# DOORLOCK_v3.net
KiCad netlist of a schematic drawn in EAGLE
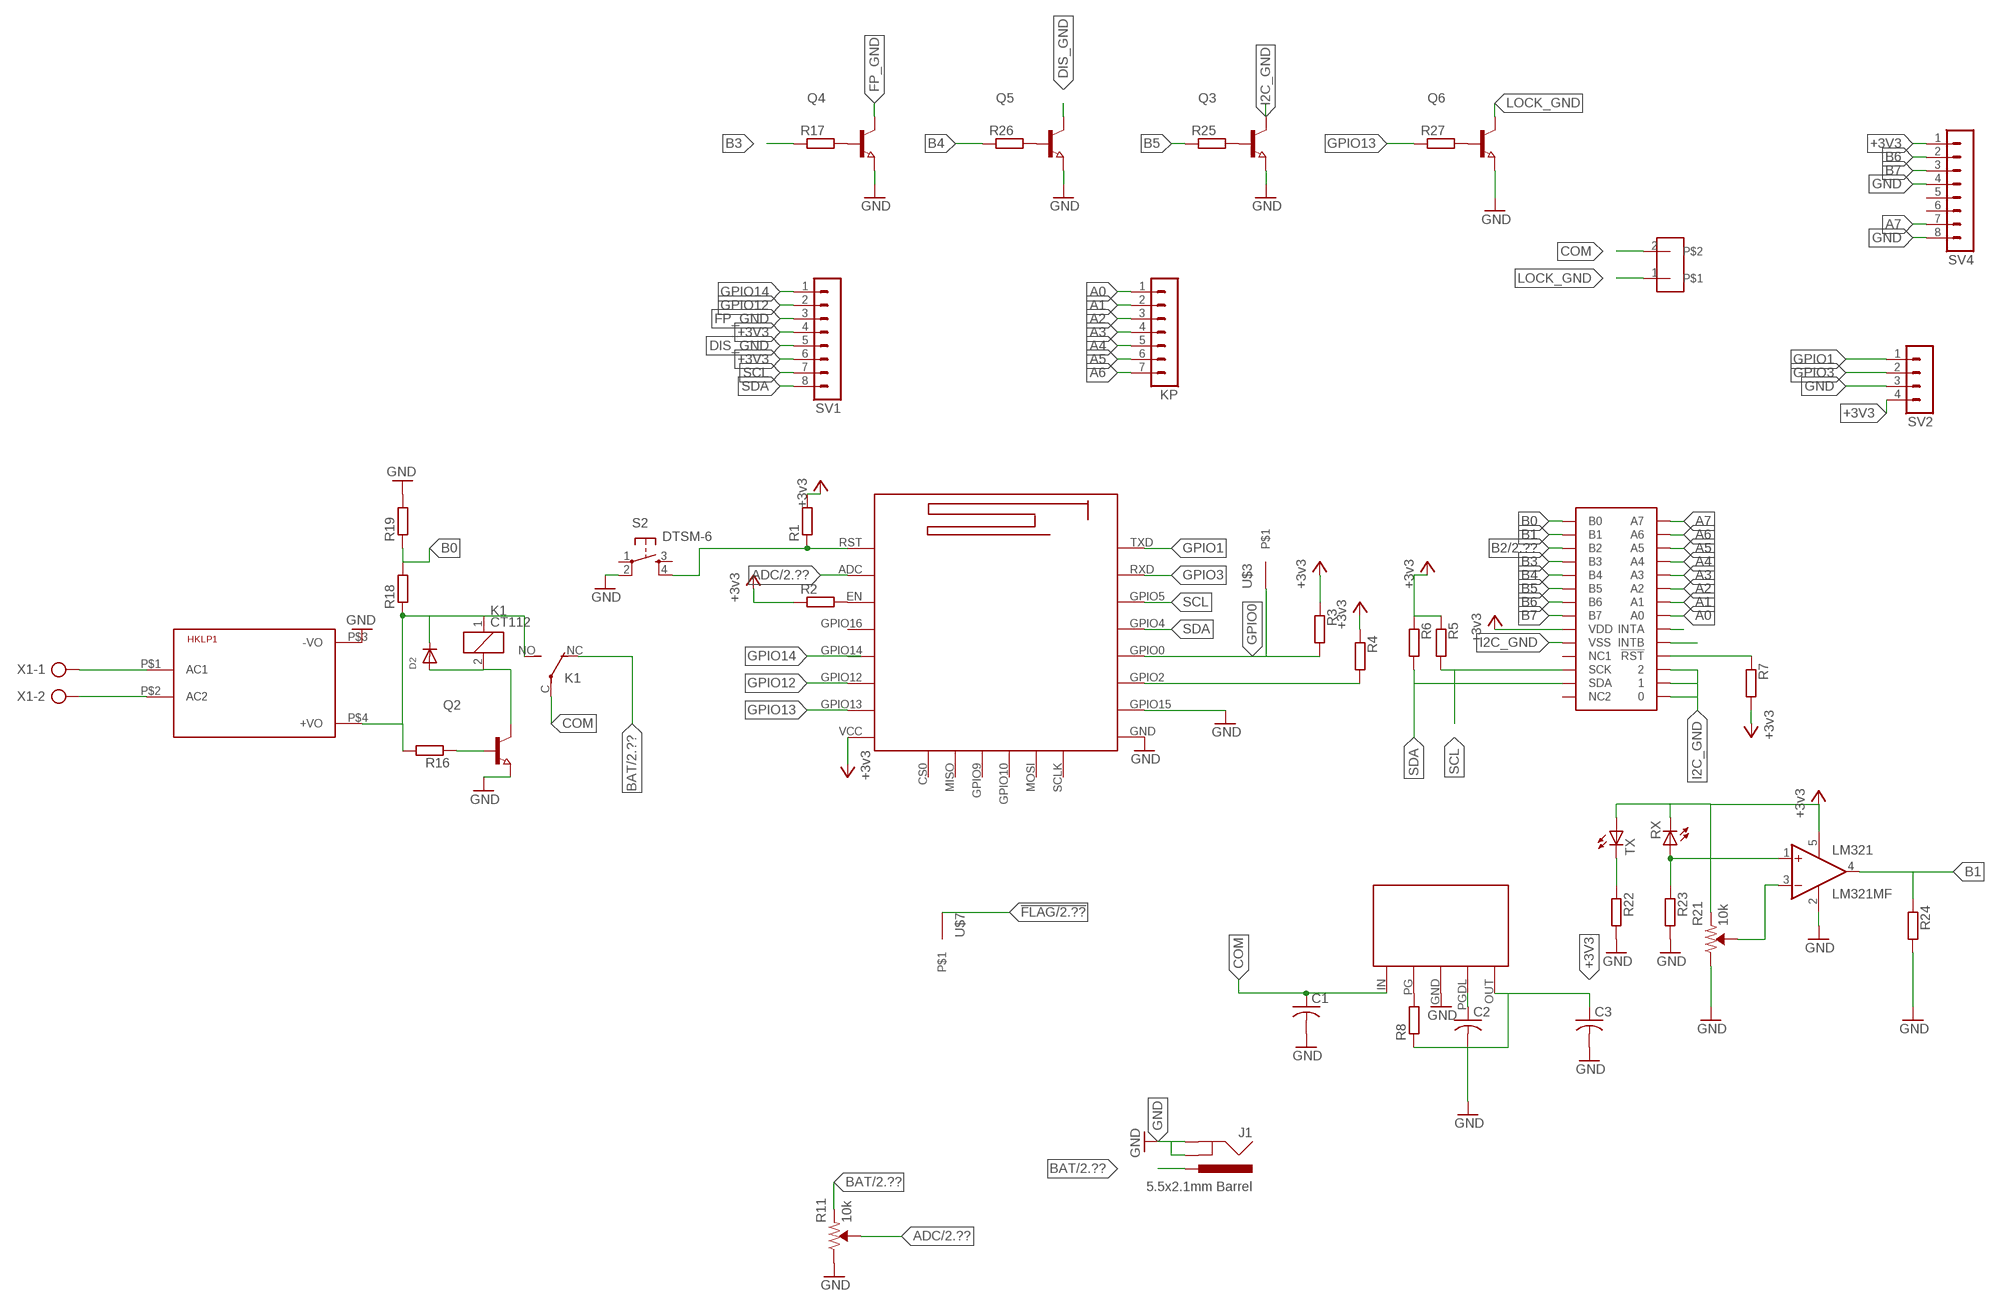
[diagram p0: schematic, sheet 1]
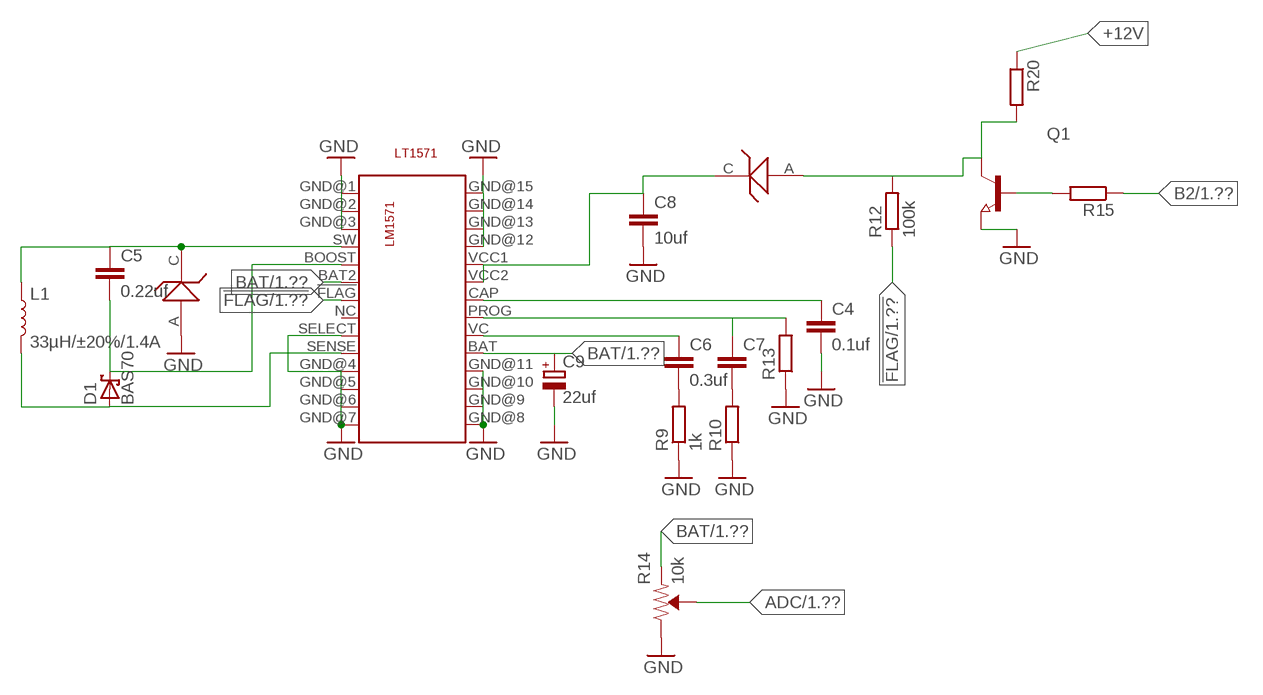
[diagram p1: schematic, sheet 2]

(export (version "E")
  (design (tool "Eeschema 10.0.6"))
  (components
    (comp (ref "C4")
      (value "0.1uf")
      (footprint "eagle-import:C0805")
      (libsource (lib "eagle-import") (part "C-EUC0805"))
    )
    (comp (ref "C5")
      (value "0.22uf")
      (footprint "eagle-import:C0805")
      (libsource (lib "eagle-import") (part "C-EUC0805"))
    )
    (comp (ref "C6")
      (value "0.3uf")
      (footprint "eagle-import:C0805")
      (libsource (lib "eagle-import") (part "C-EUC0805"))
    )
    (comp (ref "C7")
      (value "C-EUC0805")
      (footprint "eagle-import:C0805")
      (libsource (lib "eagle-import") (part "C-EUC0805"))
    )
    (comp (ref "C8")
      (value "10uf")
      (footprint "eagle-import:C0805")
      (libsource (lib "eagle-import") (part "C-EUC0805"))
    )
    (comp (ref "C9")
      (value "22uf")
      (footprint "eagle-import:CT3216")
      (libsource (lib "eagle-import") (part "CPOL-EUCT3216"))
    )
    (comp (ref "D1")
      (value "BAS70")
      (footprint "eagle-import:SOT23")
      (libsource (lib "eagle-import") (part "BAS70"))
    )
    (comp (ref "D3")
      (value "MBRM120T3")
      (footprint "eagle-import:MBRM120T3")
      (libsource (lib "eagle-import") (part "MBRM120T3"))
    )
    (comp (ref "L1")
      (value "33µH/±20%/1.4A")
      (footprint "eagle-import:SRN6045")
      (libsource (lib "eagle-import") (part "INDUCTOR-SRN6045-33UH"))
    )
    (comp (ref "LT1571")
      (value "LM1571")
      (footprint "eagle-import:LT1571")
      (libsource (lib "eagle-import") (part "LM1571"))
    )
    (comp (ref "Q1")
      (value "NPN-TRANSISTOR_SOT89")
      (footprint "eagle-import:SOT89")
      (libsource (lib "eagle-import") (part "NPN-TRANSISTOR_SOT89"))
    )
    (comp (ref "R9")
      (value "1k")
      (footprint "eagle-import:0204V")
      (libsource (lib "eagle-import") (part "R-EU_0204/2V"))
    )
    (comp (ref "R10")
      (value "R-EU_0204/2V")
      (footprint "eagle-import:0204V")
      (libsource (lib "eagle-import") (part "R-EU_0204/2V"))
    )
    (comp (ref "R12")
      (value "100k")
      (footprint "eagle-import:0204V")
      (libsource (lib "eagle-import") (part "R-EU_0204/2V"))
    )
    (comp (ref "R13")
      (value "R-EU_0204/2V")
      (footprint "eagle-import:0204V")
      (libsource (lib "eagle-import") (part "R-EU_0204/2V"))
    )
    (comp (ref "R14")
      (value "10k")
      (footprint "eagle-import:TRIMPOT-SMD-TC33X")
      (libsource (lib "eagle-import") (part "TRIMPOT-SMD-3MM-OPEN-1/10W-25%"))
    )
    (comp (ref "R15")
      (value "R-EU_0204/2V")
      (footprint "eagle-import:0204V")
      (libsource (lib "eagle-import") (part "R-EU_0204/2V"))
    )
    (comp (ref "R20")
      (value "R-EU_0204/2V")
      (footprint "eagle-import:0204V")
      (libsource (lib "eagle-import") (part "R-EU_0204/2V"))
    )
    (comp (ref "U$6")
      (value "MBRM120T3")
      (footprint "eagle-import:MBRM120T3")
      (libsource (lib "eagle-import") (part "MBRM120T3"))
    )
    (comp (ref "C1")
      (value "C-USC1206")
      (footprint "eagle-import:C1206")
      (libsource (lib "eagle-import") (part "C-USC1206"))
    )
    (comp (ref "C2")
      (value "C-USC1206")
      (footprint "eagle-import:C1206")
      (libsource (lib "eagle-import") (part "C-USC1206"))
    )
    (comp (ref "C3")
      (value "C-USC1206")
      (footprint "eagle-import:C1206")
      (libsource (lib "eagle-import") (part "C-USC1206"))
    )
    (comp (ref "D2")
      (value "DIODESOD-123")
      (footprint "eagle-import:SOD-123")
      (libsource (lib "eagle-import") (part "DIODESOD-123"))
    )
    (comp (ref "HKLP1")
      (value "HKLPM01")
      (footprint "eagle-import:HKLPM01")
      (libsource (lib "eagle-import") (part "HKLPM01"))
    )
    (comp (ref "J1")
      (value "5.5x2.1mm Barrel")
      (footprint "eagle-import:POWER_JACK_SMD")
      (libsource (lib "eagle-import") (part "POWER_JACKSMD"))
    )
    (comp (ref "K1")
      (value "CT112")
      (footprint "eagle-import:CT-SLIM")
      (libsource (lib "eagle-import") (part "CT112"))
    )
    (comp (ref "KP")
      (value "MA07-1")
      (footprint "eagle-import:MA07-1")
      (libsource (lib "eagle-import") (part "MA07-1"))
    )
    (comp (ref "LM321")
      (value "LM321MF")
      (footprint "eagle-import:SOT23-5")
      (libsource (lib "eagle-import") (part "LM321?MF"))
    )
    (comp (ref "MCP23017")
      (value "MCF23017")
      (footprint "eagle-import:MAX23017")
      (libsource (lib "eagle-import") (part "MCF23017"))
    )
    (comp (ref "MP2014")
      (value "MP2014")
      (footprint "eagle-import:MP2014")
      (libsource (lib "eagle-import") (part "MP2014"))
    )
    (comp (ref "Q2")
      (value "NPN-TRANSISTOR_SOT89")
      (footprint "eagle-import:SOT89")
      (libsource (lib "eagle-import") (part "NPN-TRANSISTOR_SOT89"))
    )
    (comp (ref "Q3")
      (value "NPN-TRANSISTOR_SOT89")
      (footprint "eagle-import:SOT89")
      (libsource (lib "eagle-import") (part "NPN-TRANSISTOR_SOT89"))
    )
    (comp (ref "Q4")
      (value "NPN-TRANSISTOR_SOT89")
      (footprint "eagle-import:SOT89")
      (libsource (lib "eagle-import") (part "NPN-TRANSISTOR_SOT89"))
    )
    (comp (ref "Q5")
      (value "NPN-TRANSISTOR_SOT89")
      (footprint "eagle-import:SOT89")
      (libsource (lib "eagle-import") (part "NPN-TRANSISTOR_SOT89"))
    )
    (comp (ref "Q6")
      (value "NPN-TRANSISTOR_SOT89")
      (footprint "eagle-import:SOT89")
      (libsource (lib "eagle-import") (part "NPN-TRANSISTOR_SOT89"))
    )
    (comp (ref "R1")
      (value "R-EU_0204/2V")
      (footprint "eagle-import:0204V")
      (libsource (lib "eagle-import") (part "resistor_R-EU_0204/2V"))
    )
    (comp (ref "R2")
      (value "R-EU_0204/2V")
      (footprint "eagle-import:0204V")
      (libsource (lib "eagle-import") (part "resistor_R-EU_0204/2V"))
    )
    (comp (ref "R3")
      (value "R-EU_0204/2V")
      (footprint "eagle-import:0204V")
      (libsource (lib "eagle-import") (part "resistor_R-EU_0204/2V"))
    )
    (comp (ref "R4")
      (value "R-EU_0204/2V")
      (footprint "eagle-import:0204V")
      (libsource (lib "eagle-import") (part "resistor_R-EU_0204/2V"))
    )
    (comp (ref "R5")
      (value "R-EU_0204/2V")
      (footprint "eagle-import:0204V")
      (libsource (lib "eagle-import") (part "resistor_R-EU_0204/2V"))
    )
    (comp (ref "R6")
      (value "R-EU_0204/2V")
      (footprint "eagle-import:0204V")
      (libsource (lib "eagle-import") (part "resistor_R-EU_0204/2V"))
    )
    (comp (ref "R7")
      (value "R-EU_0204/2V")
      (footprint "eagle-import:0204V")
      (libsource (lib "eagle-import") (part "resistor_R-EU_0204/2V"))
    )
    (comp (ref "R8")
      (value "R-EU_0204/2V")
      (footprint "eagle-import:0204V")
      (libsource (lib "eagle-import") (part "resistor_R-EU_0204/2V"))
    )
    (comp (ref "R11")
      (value "10k")
      (footprint "eagle-import:TRIMPOT-SMD-TC33X")
      (libsource (lib "eagle-import") (part "TRIMPOT-SMD-3MM-OPEN-1/10W-25%"))
    )
    (comp (ref "R16")
      (value "R-EU_0204/2V")
      (footprint "eagle-import:0204V")
      (libsource (lib "eagle-import") (part "resistor_R-EU_0204/2V"))
    )
    (comp (ref "R17")
      (value "R-EU_0204/2V")
      (footprint "eagle-import:0204V")
      (libsource (lib "eagle-import") (part "resistor_R-EU_0204/2V"))
    )
    (comp (ref "R18")
      (value "R-EU_0204/2V")
      (footprint "eagle-import:0204V")
      (libsource (lib "eagle-import") (part "resistor_R-EU_0204/2V"))
    )
    (comp (ref "R19")
      (value "R-EU_0204/2V")
      (footprint "eagle-import:0204V")
      (libsource (lib "eagle-import") (part "resistor_R-EU_0204/2V"))
    )
    (comp (ref "R21")
      (value "10k")
      (footprint "eagle-import:TRIMPOT-SMD-TC33X")
      (libsource (lib "eagle-import") (part "TRIMPOT-SMD-3MM-OPEN-1/10W-25%"))
    )
    (comp (ref "R22")
      (value "R-EU_0204/2V")
      (footprint "eagle-import:0204V")
      (libsource (lib "eagle-import") (part "resistor_R-EU_0204/2V"))
    )
    (comp (ref "R23")
      (value "R-EU_0204/2V")
      (footprint "eagle-import:0204V")
      (libsource (lib "eagle-import") (part "resistor_R-EU_0204/2V"))
    )
    (comp (ref "R24")
      (value "R-EU_0204/2V")
      (footprint "eagle-import:0204V")
      (libsource (lib "eagle-import") (part "resistor_R-EU_0204/2V"))
    )
    (comp (ref "R25")
      (value "R-EU_0204/2V")
      (footprint "eagle-import:0204V")
      (libsource (lib "eagle-import") (part "resistor_R-EU_0204/2V"))
    )
    (comp (ref "R26")
      (value "R-EU_0204/2V")
      (footprint "eagle-import:0204V")
      (libsource (lib "eagle-import") (part "resistor_R-EU_0204/2V"))
    )
    (comp (ref "R27")
      (value "R-EU_0204/2V")
      (footprint "eagle-import:0204V")
      (libsource (lib "eagle-import") (part "resistor_R-EU_0204/2V"))
    )
    (comp (ref "RX")
      (value "LED5MM")
      (footprint "eagle-import:LED5MM")
      (libsource (lib "eagle-import") (part "LED5MM"))
    )
    (comp (ref "S2")
      (value "DTSM-6")
      (footprint "eagle-import:DTSM-6")
      (libsource (lib "eagle-import") (part "DTSM-6"))
    )
    (comp (ref "SV1")
      (value "MA08-1")
      (footprint "eagle-import:MA08-1")
      (libsource (lib "eagle-import") (part "MA08-1"))
    )
    (comp (ref "SV2")
      (value "MA04-1")
      (footprint "eagle-import:MA04-1")
      (libsource (lib "eagle-import") (part "MA04-1"))
    )
    (comp (ref "SV4")
      (value "MA08-1")
      (footprint "eagle-import:MA08-1")
      (libsource (lib "eagle-import") (part "MA08-1"))
    )
    (comp (ref "TX")
      (value "LED5MM")
      (footprint "eagle-import:LED5MM")
      (libsource (lib "eagle-import") (part "LED5MM"))
    )
    (comp (ref "U$1")
      (value "ESP12E")
      (footprint "eagle-import:ESP-12E")
      (libsource (lib "eagle-import") (part "ESP12E"))
    )
    (comp (ref "U$3") (value "M1") (footprint "eagle-import:M1") (libsource (lib "eagle-import") (part "M1")))
    (comp (ref "U$4")
      (value "MALE2PIN")
      (footprint "eagle-import:MALE2PIN")
      (libsource (lib "eagle-import") (part "MALE2PIN"))
    )
    (comp (ref "U$7") (value "M1") (footprint "eagle-import:M1") (libsource (lib "eagle-import") (part "M1")))
    (comp (ref "X1")
      (value "AK500/2-H")
      (footprint "eagle-import:AK500_2-H")
      (libsource (lib "eagle-import") (part "AK500/2-H"))
    )
  )
  (nets
    (net (code "1") (name "+3V3") (class "Default")
      (node (ref "C3") (pin "1") (pinfunction "1_1") (pintype "passive"))
      (node (ref "LM321") (pin "5") (pinfunction "V+_5") (pintype "power_in"))
      (node (ref "MCP23017") (pin "P$9") (pinfunction "VDD_P$9") (pintype "bidirectional"))
      (node (ref "MP2014") (pin "OUT") (pinfunction "P$5_OUT") (pintype "bidirectional"))
      (node (ref "R1") (pin "2") (pinfunction "2_2") (pintype "passive"))
      (node (ref "R2") (pin "1") (pinfunction "1_1") (pintype "passive"))
      (node (ref "R21") (pin "3") (pinfunction "CCW_3") (pintype "passive"))
      (node (ref "R3") (pin "1") (pinfunction "1_1") (pintype "passive"))
      (node (ref "R4") (pin "1") (pinfunction "1_1") (pintype "passive"))
      (node (ref "R5") (pin "1") (pinfunction "1_1") (pintype "passive"))
      (node (ref "R6") (pin "1") (pinfunction "1_1") (pintype "passive"))
      (node (ref "R7") (pin "2") (pinfunction "2_2") (pintype "passive"))
      (node (ref "R8") (pin "1") (pinfunction "1_1") (pintype "passive"))
      (node (ref "RX") (pin "K") (pinfunction "C_K") (pintype "passive"))
      (node (ref "SV1") (pin "4") (pinfunction "4_4") (pintype "passive"))
      (node (ref "SV1") (pin "6") (pinfunction "6_6") (pintype "passive"))
      (node (ref "SV2") (pin "4") (pinfunction "4_4") (pintype "passive"))
      (node (ref "SV4") (pin "1") (pinfunction "1_1") (pintype "passive"))
      (node (ref "TX") (pin "A") (pinfunction "A_A") (pintype "passive"))
      (node (ref "U$1") (pin "VCC") (pinfunction "P$8_VCC") (pintype "bidirectional"))
    )
    (net (code "2") (name "+12V") (class "Default")
      (node (ref "D2") (pin "C") (pinfunction "C_C") (pintype "passive"))
      (node (ref "HKLP1") (pin "P$4") (pinfunction "+VO_P$4") (pintype "bidirectional"))
      (node (ref "K1") (pin "1") (pinfunction "1_1") (pintype "passive"))
      (node (ref "K1") (pin "NO") (pinfunction "S_NO") (pintype "passive"))
      (node (ref "R16") (pin "2") (pinfunction "2_2") (pintype "passive"))
      (node (ref "R18") (pin "1") (pinfunction "1_1") (pintype "passive"))
      (node (ref "R20") (pin "1") (pinfunction "1_1") (pintype "passive"))
    )
    (net (code "3") (name "A0") (class "Default")
      (node (ref "KP") (pin "1") (pinfunction "1_1") (pintype "passive"))
      (node (ref "MCP23017") (pin "P$21") (pinfunction "A0_P$21") (pintype "bidirectional"))
    )
    (net (code "4") (name "A1") (class "Default")
      (node (ref "KP") (pin "2") (pinfunction "2_2") (pintype "passive"))
      (node (ref "MCP23017") (pin "P$22") (pinfunction "A1_P$22") (pintype "bidirectional"))
    )
    (net (code "5") (name "A2") (class "Default")
      (node (ref "KP") (pin "3") (pinfunction "3_3") (pintype "passive"))
      (node (ref "MCP23017") (pin "P$23") (pinfunction "A2_P$23") (pintype "bidirectional"))
    )
    (net (code "6") (name "A3") (class "Default")
      (node (ref "KP") (pin "4") (pinfunction "4_4") (pintype "passive"))
      (node (ref "MCP23017") (pin "P$24") (pinfunction "A3_P$24") (pintype "bidirectional"))
    )
    (net (code "7") (name "A4") (class "Default")
      (node (ref "KP") (pin "5") (pinfunction "5_5") (pintype "passive"))
      (node (ref "MCP23017") (pin "P$25") (pinfunction "A4_P$25") (pintype "bidirectional"))
    )
    (net (code "8") (name "A5") (class "Default")
      (node (ref "KP") (pin "6") (pinfunction "6_6") (pintype "passive"))
      (node (ref "MCP23017") (pin "P$26") (pinfunction "A5_P$26") (pintype "bidirectional"))
    )
    (net (code "9") (name "A6") (class "Default")
      (node (ref "KP") (pin "7") (pinfunction "7_7") (pintype "passive"))
      (node (ref "MCP23017") (pin "P$27") (pinfunction "A6_P$27") (pintype "bidirectional"))
    )
    (net (code "10") (name "A7") (class "Default")
      (node (ref "MCP23017") (pin "P$28") (pinfunction "A7_P$28") (pintype "bidirectional"))
      (node (ref "SV4") (pin "7") (pinfunction "7_7") (pintype "passive"))
    )
    (net (code "11") (name "ADC") (class "Default")
      (node (ref "R11") (pin "2") (pinfunction "WIPER_2") (pintype "passive"))
      (node (ref "R14") (pin "2") (pinfunction "WIPER_2") (pintype "passive"))
      (node (ref "U$1") (pin "ADC") (pinfunction "P$2_ADC") (pintype "bidirectional"))
    )
    (net (code "12") (name "B0") (class "Default")
      (node (ref "MCP23017") (pin "P$1") (pinfunction "B0_P$1") (pintype "bidirectional"))
      (node (ref "R18") (pin "2") (pinfunction "2_2") (pintype "passive"))
      (node (ref "R19") (pin "1") (pinfunction "1_1") (pintype "passive"))
    )
    (net (code "13") (name "B1") (class "Default")
      (node (ref "LM321") (pin "4") (pinfunction "OUT_4") (pintype "output"))
      (node (ref "MCP23017") (pin "P$2") (pinfunction "B1_P$2") (pintype "bidirectional"))
      (node (ref "R24") (pin "1") (pinfunction "1_1") (pintype "passive"))
    )
    (net (code "14") (name "B2") (class "Default")
      (node (ref "MCP23017") (pin "P$3") (pinfunction "B2_P$3") (pintype "bidirectional"))
      (node (ref "R15") (pin "1") (pinfunction "1_1") (pintype "passive"))
    )
    (net (code "15") (name "B3") (class "Default")
      (node (ref "MCP23017") (pin "P$4") (pinfunction "B3_P$4") (pintype "bidirectional"))
      (node (ref "R17") (pin "1") (pinfunction "1_1") (pintype "passive"))
    )
    (net (code "16") (name "B4") (class "Default")
      (node (ref "MCP23017") (pin "P$5") (pinfunction "B4_P$5") (pintype "bidirectional"))
      (node (ref "R26") (pin "1") (pinfunction "1_1") (pintype "passive"))
    )
    (net (code "17") (name "B5") (class "Default")
      (node (ref "MCP23017") (pin "P$6") (pinfunction "B5_P$6") (pintype "bidirectional"))
      (node (ref "R25") (pin "1") (pinfunction "1_1") (pintype "passive"))
    )
    (net (code "18") (name "B6") (class "Default")
      (node (ref "MCP23017") (pin "P$7") (pinfunction "B6_P$7") (pintype "bidirectional"))
      (node (ref "SV4") (pin "2") (pinfunction "2_2") (pintype "passive"))
    )
    (net (code "19") (name "B7") (class "Default")
      (node (ref "MCP23017") (pin "P$8") (pinfunction "B7_P$8") (pintype "bidirectional"))
      (node (ref "SV4") (pin "3") (pinfunction "3_3") (pintype "passive"))
    )
    (net (code "20") (name "BAT") (class "Default")
      (node (ref "C9") (pin "+") (pinfunction "+_+") (pintype "passive"))
      (node (ref "J1") (pin "VIN0") (pinfunction "PWR_VIN0") (pintype "bidirectional"))
      (node (ref "K1") (pin "NC") (pinfunction "O_NC") (pintype "passive"))
      (node (ref "LT1571") (pin "BAT") (pinfunction "P$19_BAT") (pintype "bidirectional"))
      (node (ref "LT1571") (pin "BAT2") (pinfunction "P$6_BAT2") (pintype "bidirectional"))
      (node (ref "R11") (pin "3") (pinfunction "CCW_3") (pintype "passive"))
      (node (ref "R14") (pin "3") (pinfunction "CCW_3") (pintype "passive"))
    )
    (net (code "21") (name "COM") (class "Default")
      (node (ref "C1") (pin "1") (pinfunction "1_1") (pintype "passive"))
      (node (ref "K1") (pin "C") (pinfunction "P_C") (pintype "passive"))
      (node (ref "MP2014") (pin "IN") (pinfunction "P$1_IN") (pintype "bidirectional"))
      (node (ref "U$4") (pin "2") (pinfunction "P$2_2") (pintype "bidirectional"))
    )
    (net (code "22") (name "DIS_GND") (class "Default")
      (node (ref "Q5") (pin "2") (pinfunction "C_2") (pintype "passive"))
      (node (ref "SV1") (pin "5") (pinfunction "5_5") (pintype "passive"))
    )
    (net (code "23") (name "FP_GND") (class "Default")
      (node (ref "Q4") (pin "2") (pinfunction "C_2") (pintype "passive"))
      (node (ref "SV1") (pin "3") (pinfunction "3_3") (pintype "passive"))
    )
    (net (code "24") (name "GND") (class "Default")
      (node (ref "C1") (pin "2") (pinfunction "2_2") (pintype "passive"))
      (node (ref "C2") (pin "2") (pinfunction "2_2") (pintype "passive"))
      (node (ref "C3") (pin "2") (pinfunction "2_2") (pintype "passive"))
      (node (ref "C4") (pin "2") (pinfunction "2_2") (pintype "passive"))
      (node (ref "C8") (pin "2") (pinfunction "2_2") (pintype "passive"))
      (node (ref "C9") (pin "-") (pinfunction "-_-") (pintype "passive"))
      (node (ref "HKLP1") (pin "P$3") (pinfunction "-VO_P$3") (pintype "bidirectional"))
      (node (ref "J1") (pin "GND") (pinfunction "GNDBREAK_GND") (pintype "bidirectional"))
      (node (ref "J1") (pin "P$4") (pinfunction "GND_P$4") (pintype "bidirectional"))
      (node (ref "LM321") (pin "2") (pinfunction "V-_2") (pintype "power_in"))
      (node (ref "LT1571") (pin "GND@1") (pinfunction "P$1_GND@1") (pintype "bidirectional"))
      (node (ref "LT1571") (pin "GND@10") (pinfunction "P$17_GND@10") (pintype "bidirectional"))
      (node (ref "LT1571") (pin "GND@11") (pinfunction "P$18_GND@11") (pintype "bidirectional"))
      (node (ref "LT1571") (pin "GND@12") (pinfunction "P$25_GND@12") (pintype "bidirectional"))
      (node (ref "LT1571") (pin "GND@13") (pinfunction "P$26_GND@13") (pintype "bidirectional"))
      (node (ref "LT1571") (pin "GND@14") (pinfunction "P$27_GND@14") (pintype "bidirectional"))
      (node (ref "LT1571") (pin "GND@15") (pinfunction "P$28_GND@15") (pintype "bidirectional"))
      (node (ref "LT1571") (pin "GND@2") (pinfunction "P$2_GND@2") (pintype "bidirectional"))
      (node (ref "LT1571") (pin "GND@3") (pinfunction "P$3_GND@3") (pintype "bidirectional"))
      (node (ref "LT1571") (pin "GND@4") (pinfunction "P$11_GND@4") (pintype "bidirectional"))
      (node (ref "LT1571") (pin "GND@5") (pinfunction "P$12_GND@5") (pintype "bidirectional"))
      (node (ref "LT1571") (pin "GND@6") (pinfunction "P$13_GND@6") (pintype "bidirectional"))
      (node (ref "LT1571") (pin "GND@7") (pinfunction "P$14_GND@7") (pintype "bidirectional"))
      (node (ref "LT1571") (pin "GND@8") (pinfunction "P$15_GND@8") (pintype "bidirectional"))
      (node (ref "LT1571") (pin "GND@9") (pinfunction "P$16_GND@9") (pintype "bidirectional"))
      (node (ref "LT1571") (pin "SELECT") (pinfunction "P$9_SELECT") (pintype "bidirectional"))
      (node (ref "MP2014") (pin "GND") (pinfunction "P$3_GND") (pintype "bidirectional"))
      (node (ref "Q1") (pin "3") (pinfunction "E_3") (pintype "passive"))
      (node (ref "Q2") (pin "3") (pinfunction "E_3") (pintype "passive"))
      (node (ref "Q3") (pin "3") (pinfunction "E_3") (pintype "passive"))
      (node (ref "Q4") (pin "3") (pinfunction "E_3") (pintype "passive"))
      (node (ref "Q5") (pin "3") (pinfunction "E_3") (pintype "passive"))
      (node (ref "Q6") (pin "3") (pinfunction "E_3") (pintype "passive"))
      (node (ref "R10") (pin "1") (pinfunction "1_1") (pintype "passive"))
      (node (ref "R11") (pin "1") (pinfunction "CW_1") (pintype "passive"))
      (node (ref "R13") (pin "1") (pinfunction "1_1") (pintype "passive"))
      (node (ref "R14") (pin "1") (pinfunction "CW_1") (pintype "passive"))
      (node (ref "R19") (pin "2") (pinfunction "2_2") (pintype "passive"))
      (node (ref "R21") (pin "1") (pinfunction "CW_1") (pintype "passive"))
      (node (ref "R22") (pin "2") (pinfunction "2_2") (pintype "passive"))
      (node (ref "R23") (pin "2") (pinfunction "2_2") (pintype "passive"))
      (node (ref "R24") (pin "2") (pinfunction "2_2") (pintype "passive"))
      (node (ref "R9") (pin "1") (pinfunction "1_1") (pintype "passive"))
      (node (ref "S2") (pin "2") (pinfunction "2_2") (pintype "passive"))
      (node (ref "SV2") (pin "3") (pinfunction "3_3") (pintype "passive"))
      (node (ref "SV4") (pin "4") (pinfunction "4_4") (pintype "passive"))
      (node (ref "SV4") (pin "8") (pinfunction "8_8") (pintype "passive"))
      (node (ref "U$1") (pin "GND") (pinfunction "P$15_GND") (pintype "bidirectional"))
      (node (ref "U$1") (pin "GPIO15") (pinfunction "P$16_GPIO15") (pintype "bidirectional"))
      (node (ref "U$6") (pin "A") (pinfunction "A_A") (pintype "bidirectional"))
    )
    (net (code "25") (name "GPIO0") (class "Default")
      (node (ref "R3") (pin "2") (pinfunction "2_2") (pintype "passive"))
      (node (ref "U$1") (pin "GPIO0") (pinfunction "P$18_GPIO0") (pintype "bidirectional"))
      (node (ref "U$3") (pin "P$1") (pinfunction "P$1_P$1") (pintype "bidirectional"))
    )
    (net (code "26") (name "GPIO1") (class "Default")
      (node (ref "SV2") (pin "1") (pinfunction "1_1") (pintype "passive"))
      (node (ref "U$1") (pin "TXD") (pinfunction "P$22_TXD") (pintype "bidirectional"))
    )
    (net (code "27") (name "GPIO3") (class "Default")
      (node (ref "SV2") (pin "2") (pinfunction "2_2") (pintype "passive"))
      (node (ref "U$1") (pin "RXD") (pinfunction "P$21_RXD") (pintype "bidirectional"))
    )
    (net (code "28") (name "GPIO12") (class "Default")
      (node (ref "SV1") (pin "2") (pinfunction "2_2") (pintype "passive"))
      (node (ref "U$1") (pin "GPIO12") (pinfunction "P$6_GPIO12") (pintype "bidirectional"))
    )
    (net (code "29") (name "GPIO13") (class "Default")
      (node (ref "R27") (pin "1") (pinfunction "1_1") (pintype "passive"))
      (node (ref "U$1") (pin "GPIO13") (pinfunction "P$7_GPIO13") (pintype "bidirectional"))
    )
    (net (code "30") (name "GPIO14") (class "Default")
      (node (ref "SV1") (pin "1") (pinfunction "1_1") (pintype "passive"))
      (node (ref "U$1") (pin "GPIO14") (pinfunction "P$5_GPIO14") (pintype "bidirectional"))
    )
    (net (code "31") (name "I2C_GND") (class "Default")
      (node (ref "MCP23017") (pin "P$10") (pinfunction "VSS_P$10") (pintype "bidirectional"))
      (node (ref "MCP23017") (pin "P$15") (pinfunction "0_P$15") (pintype "bidirectional"))
      (node (ref "MCP23017") (pin "P$16") (pinfunction "1_P$16") (pintype "bidirectional"))
      (node (ref "MCP23017") (pin "P$17") (pinfunction "2_P$17") (pintype "bidirectional"))
      (node (ref "Q3") (pin "2") (pinfunction "C_2") (pintype "passive"))
    )
    (net (code "32") (name "LOCK_GND") (class "Default")
      (node (ref "Q6") (pin "2") (pinfunction "C_2") (pintype "passive"))
      (node (ref "U$4") (pin "1") (pinfunction "P$1_1") (pintype "bidirectional"))
    )
    (net (code "33") (name "Net-(C6-Pad2)") (class "Default")
      (node (ref "C6") (pin "2") (pinfunction "2_2") (pintype "passive"))
      (node (ref "R9") (pin "2") (pinfunction "2_2") (pintype "passive"))
    )
    (net (code "34") (name "Net-(C7-Pad2)") (class "Default")
      (node (ref "C7") (pin "2") (pinfunction "2_2") (pintype "passive"))
      (node (ref "R10") (pin "2") (pinfunction "2_2") (pintype "passive"))
    )
    (net (code "35") (name "Net-(D1-A)") (class "Default")
      (node (ref "D1") (pin "1") (pinfunction "A_1") (pintype "passive"))
      (node (ref "L1") (pin "2") (pinfunction "2_2") (pintype "passive"))
      (node (ref "LT1571") (pin "SENSE") (pinfunction "P$10_SENSE") (pintype "bidirectional"))
    )
    (net (code "36") (name "Net-(D1-C)") (class "Default")
      (node (ref "C5") (pin "2") (pinfunction "2_2") (pintype "passive"))
      (node (ref "D1") (pin "3") (pinfunction "C_3") (pintype "passive"))
      (node (ref "LT1571") (pin "BOOST") (pinfunction "P$5_BOOST") (pintype "bidirectional"))
    )
    (net (code "37") (name "Net-(HKLP1-AC1)") (class "Default")
      (node (ref "HKLP1") (pin "P$1") (pinfunction "AC1_P$1") (pintype "bidirectional"))
      (node (ref "X1") (pin "1") (pinfunction "KL_1") (pintype "passive"))
    )
    (net (code "38") (name "Net-(HKLP1-AC2)") (class "Default")
      (node (ref "HKLP1") (pin "P$2") (pinfunction "AC2_P$2") (pintype "bidirectional"))
      (node (ref "X1") (pin "2") (pinfunction "KL_2") (pintype "passive"))
    )
    (net (code "39") (name "Net-(LM321-+IN)") (class "Default")
      (node (ref "LM321") (pin "1") (pinfunction "+IN_1") (pintype "input"))
      (node (ref "R23") (pin "1") (pinfunction "1_1") (pintype "passive"))
      (node (ref "RX") (pin "A") (pinfunction "A_A") (pintype "passive"))
    )
    (net (code "40") (name "Net-(LM321--IN)") (class "Default")
      (node (ref "LM321") (pin "3") (pinfunction "-IN_3") (pintype "input"))
      (node (ref "R21") (pin "2") (pinfunction "WIPER_2") (pintype "passive"))
    )
    (net (code "41") (name "Net-(LT1571-P$4)") (class "Default")
      (node (ref "C5") (pin "1") (pinfunction "1_1") (pintype "passive"))
      (node (ref "L1") (pin "1") (pinfunction "1_1") (pintype "passive"))
      (node (ref "LT1571") (pin "SW") (pinfunction "P$4_SW") (pintype "bidirectional"))
      (node (ref "U$6") (pin "C") (pinfunction "C_C") (pintype "bidirectional"))
    )
    (net (code "42") (name "Net-(LT1571-P$20)") (class "Default")
      (node (ref "C6") (pin "1") (pinfunction "1_1") (pintype "passive"))
      (node (ref "LT1571") (pin "VC") (pinfunction "P$20_VC") (pintype "bidirectional"))
    )
    (net (code "43") (name "Net-(LT1571-P$21)") (class "Default")
      (node (ref "C7") (pin "1") (pinfunction "1_1") (pintype "passive"))
      (node (ref "LT1571") (pin "PROG") (pinfunction "P$21_PROG") (pintype "bidirectional"))
      (node (ref "R13") (pin "2") (pinfunction "2_2") (pintype "passive"))
    )
    (net (code "44") (name "Net-(LT1571-P$22)") (class "Default")
      (node (ref "C4") (pin "1") (pinfunction "1_1") (pintype "passive"))
      (node (ref "LT1571") (pin "CAP") (pinfunction "P$22_CAP") (pintype "bidirectional"))
    )
    (net (code "45") (name "Net-(LT1571-P$23)") (class "Default")
      (node (ref "C8") (pin "1") (pinfunction "1_1") (pintype "passive"))
      (node (ref "D3") (pin "C") (pinfunction "C_C") (pintype "bidirectional"))
      (node (ref "LT1571") (pin "VCC1") (pinfunction "P$24_VCC1") (pintype "bidirectional"))
      (node (ref "LT1571") (pin "VCC2") (pinfunction "P$23_VCC2") (pintype "bidirectional"))
    )
    (net (code "46") (name "Net-(MCP23017-~{RST})") (class "Default")
      (node (ref "MCP23017") (pin "P$18") (pinfunction "~{RST}_P$18") (pintype "bidirectional"))
      (node (ref "R7") (pin "1") (pinfunction "1_1") (pintype "passive"))
    )
    (net (code "47") (name "Net-(MP2014-P$2)") (class "Default")
      (node (ref "MP2014") (pin "PG") (pinfunction "P$2_PG") (pintype "bidirectional"))
      (node (ref "R8") (pin "2") (pinfunction "2_2") (pintype "passive"))
    )
    (net (code "48") (name "Net-(MP2014-P$4)") (class "Default")
      (node (ref "C2") (pin "1") (pinfunction "1_1") (pintype "passive"))
      (node (ref "MP2014") (pin "PGDL") (pinfunction "P$4_PGDL") (pintype "bidirectional"))
    )
    (net (code "49") (name "Net-(Q1-B)") (class "Default")
      (node (ref "Q1") (pin "1") (pinfunction "B_1") (pintype "passive"))
      (node (ref "R15") (pin "2") (pinfunction "2_2") (pintype "passive"))
    )
    (net (code "50") (name "Net-(Q1-C)") (class "Default")
      (node (ref "D3") (pin "A") (pinfunction "A_A") (pintype "bidirectional"))
      (node (ref "Q1") (pin "2") (pinfunction "C_2") (pintype "passive"))
      (node (ref "R12") (pin "2") (pinfunction "2_2") (pintype "passive"))
      (node (ref "R20") (pin "2") (pinfunction "2_2") (pintype "passive"))
    )
    (net (code "51") (name "Net-(Q2-B)") (class "Default")
      (node (ref "Q2") (pin "1") (pinfunction "B_1") (pintype "passive"))
      (node (ref "R16") (pin "1") (pinfunction "1_1") (pintype "passive"))
    )
    (net (code "52") (name "Net-(Q2-C)") (class "Default")
      (node (ref "D2") (pin "A") (pinfunction "A_A") (pintype "passive"))
      (node (ref "K1") (pin "2") (pinfunction "2_2") (pintype "passive"))
      (node (ref "Q2") (pin "2") (pinfunction "C_2") (pintype "passive"))
    )
    (net (code "53") (name "Net-(Q3-B)") (class "Default")
      (node (ref "Q3") (pin "1") (pinfunction "B_1") (pintype "passive"))
      (node (ref "R25") (pin "2") (pinfunction "2_2") (pintype "passive"))
    )
    (net (code "54") (name "Net-(Q4-B)") (class "Default")
      (node (ref "Q4") (pin "1") (pinfunction "B_1") (pintype "passive"))
      (node (ref "R17") (pin "2") (pinfunction "2_2") (pintype "passive"))
    )
    (net (code "55") (name "Net-(Q5-B)") (class "Default")
      (node (ref "Q5") (pin "1") (pinfunction "B_1") (pintype "passive"))
      (node (ref "R26") (pin "2") (pinfunction "2_2") (pintype "passive"))
    )
    (net (code "56") (name "Net-(Q6-B)") (class "Default")
      (node (ref "Q6") (pin "1") (pinfunction "B_1") (pintype "passive"))
      (node (ref "R27") (pin "2") (pinfunction "2_2") (pintype "passive"))
    )
    (net (code "57") (name "Net-(TX-C)") (class "Default")
      (node (ref "R22") (pin "1") (pinfunction "1_1") (pintype "passive"))
      (node (ref "TX") (pin "K") (pinfunction "C_K") (pintype "passive"))
    )
    (net (code "58") (name "Net-(U$1-P$1)") (class "Default")
      (node (ref "R1") (pin "1") (pinfunction "1_1") (pintype "passive"))
      (node (ref "S2") (pin "4") (pinfunction "4_4") (pintype "passive"))
      (node (ref "U$1") (pin "RST") (pinfunction "P$1_RST") (pintype "bidirectional"))
    )
    (net (code "59") (name "Net-(U$1-P$3)") (class "Default")
      (node (ref "R2") (pin "2") (pinfunction "2_2") (pintype "passive"))
      (node (ref "U$1") (pin "EN") (pinfunction "P$3_EN") (pintype "bidirectional"))
    )
    (net (code "60") (name "Net-(U$1-P$17)") (class "Default")
      (node (ref "R4") (pin "2") (pinfunction "2_2") (pintype "passive"))
      (node (ref "U$1") (pin "GPIO2") (pinfunction "P$17_GPIO2") (pintype "bidirectional"))
    )
    (net (code "61") (name "SCL") (class "Default")
      (node (ref "MCP23017") (pin "P$12") (pinfunction "SCK_P$12") (pintype "bidirectional"))
      (node (ref "R5") (pin "2") (pinfunction "2_2") (pintype "passive"))
      (node (ref "SV1") (pin "7") (pinfunction "7_7") (pintype "passive"))
      (node (ref "U$1") (pin "GPIO5") (pinfunction "P$20_GPIO5") (pintype "bidirectional"))
    )
    (net (code "62") (name "SDA") (class "Default")
      (node (ref "MCP23017") (pin "P$13") (pinfunction "SDA_P$13") (pintype "bidirectional"))
      (node (ref "R6") (pin "2") (pinfunction "2_2") (pintype "passive"))
      (node (ref "SV1") (pin "8") (pinfunction "8_8") (pintype "passive"))
      (node (ref "U$1") (pin "GPIO4") (pinfunction "P$19_GPIO4") (pintype "bidirectional"))
    )
    (net (code "63") (name "unconnected-(LT1571-P$8-PadNC)") (class "Default")
      (node (ref "LT1571") (pin "NC") (pinfunction "P$8_NC") (pintype "bidirectional"))
    )
    (net (code "64") (name "unconnected-(MCP23017-INTA-PadP$20)") (class "Default")
      (node (ref "MCP23017") (pin "P$20") (pinfunction "INTA_P$20") (pintype "bidirectional"))
    )
    (net (code "65") (name "unconnected-(MCP23017-INTB-PadP$19)") (class "Default")
      (node (ref "MCP23017") (pin "P$19") (pinfunction "INTB_P$19") (pintype "bidirectional"))
    )
    (net (code "66") (name "unconnected-(MCP23017-NC1-PadP$11)") (class "Default")
      (node (ref "MCP23017") (pin "P$11") (pinfunction "NC1_P$11") (pintype "bidirectional"))
    )
    (net (code "67") (name "unconnected-(MCP23017-NC2-PadP$14)") (class "Default")
      (node (ref "MCP23017") (pin "P$14") (pinfunction "NC2_P$14") (pintype "bidirectional"))
    )
    (net (code "68") (name "unconnected-(S2-Pad1)") (class "Default")
      (node (ref "S2") (pin "1") (pinfunction "1_1") (pintype "passive"))
    )
    (net (code "69") (name "unconnected-(S2-Pad3)") (class "Default")
      (node (ref "S2") (pin "3") (pinfunction "3_3") (pintype "passive"))
    )
    (net (code "70") (name "unconnected-(SV4-Pad5)") (class "Default")
      (node (ref "SV4") (pin "5") (pinfunction "5_5") (pintype "passive"))
    )
    (net (code "71") (name "unconnected-(SV4-Pad6)") (class "Default")
      (node (ref "SV4") (pin "6") (pinfunction "6_6") (pintype "passive"))
    )
    (net (code "72") (name "unconnected-(U$1-P$4-PadGPIO16)") (class "Default")
      (node (ref "U$1") (pin "GPIO16") (pinfunction "P$4_GPIO16") (pintype "bidirectional"))
    )
    (net (code "73") (name "unconnected-(U$1-P$9-PadCS0)") (class "Default")
      (node (ref "U$1") (pin "CS0") (pinfunction "P$9_CS0") (pintype "bidirectional"))
    )
    (net (code "74") (name "unconnected-(U$1-P$10-PadMISO)") (class "Default")
      (node (ref "U$1") (pin "MISO") (pinfunction "P$10_MISO") (pintype "bidirectional"))
    )
    (net (code "75") (name "unconnected-(U$1-P$11-PadGPIO9)") (class "Default")
      (node (ref "U$1") (pin "GPIO9") (pinfunction "P$11_GPIO9") (pintype "bidirectional"))
    )
    (net (code "76") (name "unconnected-(U$1-P$12-PadGPIO10)") (class "Default")
      (node (ref "U$1") (pin "GPIO10") (pinfunction "P$12_GPIO10") (pintype "bidirectional"))
    )
    (net (code "77") (name "unconnected-(U$1-P$13-PadMOSI)") (class "Default")
      (node (ref "U$1") (pin "MOSI") (pinfunction "P$13_MOSI") (pintype "bidirectional"))
    )
    (net (code "78") (name "unconnected-(U$1-P$14-PadSCLK)") (class "Default")
      (node (ref "U$1") (pin "SCLK") (pinfunction "P$14_SCLK") (pintype "bidirectional"))
    )
    (net (code "79") (name "~{FLAG}") (class "Default")
      (node (ref "LT1571") (pin "!FLAG") (pinfunction "P$7_!FLAG") (pintype "bidirectional"))
      (node (ref "R12") (pin "1") (pinfunction "1_1") (pintype "passive"))
      (node (ref "U$7") (pin "P$1") (pinfunction "P$1_P$1") (pintype "bidirectional"))
    )
  )
)
